# Lan_Tap_V1.net
KiCad netlist of a schematic drawn in EAGLE
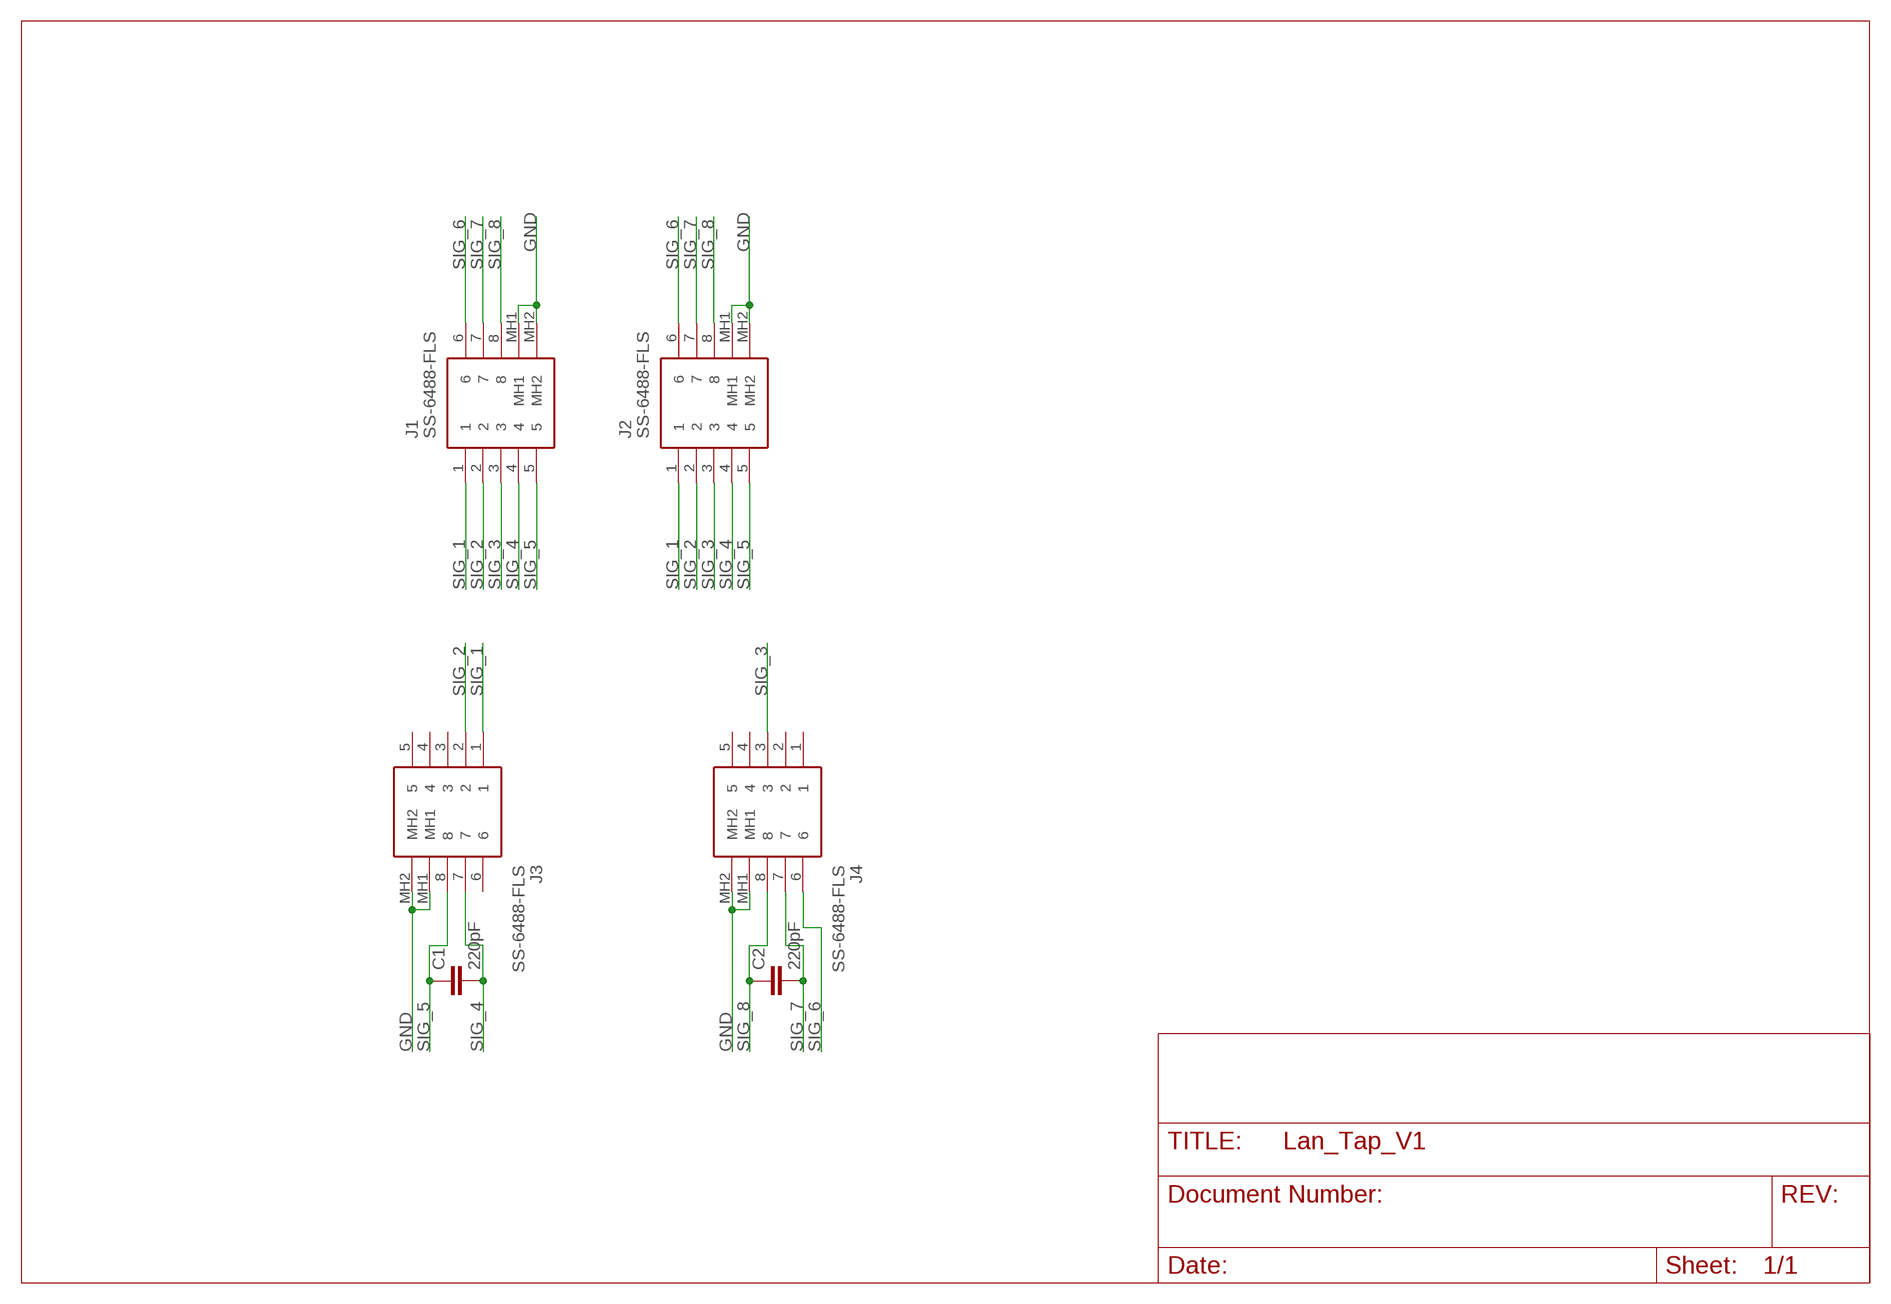
[diagram p0: schematic, sheet 1]

(export (version "E")
  (design (tool "Eeschema 10.0.6"))
  (components
    (comp (ref "C1")
      (value "220pF")
      (footprint "eagle-import:C2.5-2")
      (libsource (lib "eagle-import") (part "C2.5/2"))
    )
    (comp (ref "C2")
      (value "220pF")
      (footprint "eagle-import:C2.5-2")
      (libsource (lib "eagle-import") (part "C2.5/2"))
    )
    (comp (ref "J1")
      (value "SS-6488-FLS")
      (footprint "eagle-import:SS6488FLS")
      (fields (field (name "MOUSER_PART_NUMBER") "530-SS-6488-FLS"))
      (libsource (lib "eagle-import") (part "SS-6488-FLS"))
    )
    (comp (ref "J2")
      (value "SS-6488-FLS")
      (footprint "eagle-import:SS6488FLS")
      (fields (field (name "MOUSER_PART_NUMBER") "530-SS-6488-FLS"))
      (libsource (lib "eagle-import") (part "SS-6488-FLS"))
    )
    (comp (ref "J3")
      (value "SS-6488-FLS")
      (footprint "eagle-import:SS6488FLS")
      (fields (field (name "MOUSER_PART_NUMBER") "530-SS-6488-FLS"))
      (libsource (lib "eagle-import") (part "SS-6488-FLS"))
    )
    (comp (ref "J4")
      (value "SS-6488-FLS")
      (footprint "eagle-import:SS6488FLS")
      (fields (field (name "MOUSER_PART_NUMBER") "530-SS-6488-FLS"))
      (libsource (lib "eagle-import") (part "SS-6488-FLS"))
    )
  )
  (nets
    (net (code "1") (name "/GND") (class "Default")
      (node (ref "J1") (pin "MH1") (pinfunction "MH1_MH1") (pintype "bidirectional"))
      (node (ref "J1") (pin "MH2") (pinfunction "MH2_MH2") (pintype "bidirectional"))
      (node (ref "J2") (pin "MH1") (pinfunction "MH1_MH1") (pintype "bidirectional"))
      (node (ref "J2") (pin "MH2") (pinfunction "MH2_MH2") (pintype "bidirectional"))
      (node (ref "J3") (pin "MH1") (pinfunction "MH1_MH1") (pintype "bidirectional"))
      (node (ref "J3") (pin "MH2") (pinfunction "MH2_MH2") (pintype "bidirectional"))
      (node (ref "J4") (pin "MH1") (pinfunction "MH1_MH1") (pintype "bidirectional"))
      (node (ref "J4") (pin "MH2") (pinfunction "MH2_MH2") (pintype "bidirectional"))
    )
    (net (code "2") (name "/SIG_1") (class "Default")
      (node (ref "J1") (pin "1") (pinfunction "1_1") (pintype "bidirectional"))
      (node (ref "J2") (pin "1") (pinfunction "1_1") (pintype "bidirectional"))
      (node (ref "J3") (pin "1") (pinfunction "1_1") (pintype "bidirectional"))
    )
    (net (code "3") (name "/SIG_2") (class "Default")
      (node (ref "J1") (pin "2") (pinfunction "2_2") (pintype "bidirectional"))
      (node (ref "J2") (pin "2") (pinfunction "2_2") (pintype "bidirectional"))
      (node (ref "J3") (pin "2") (pinfunction "2_2") (pintype "bidirectional"))
    )
    (net (code "4") (name "/SIG_3") (class "Default")
      (node (ref "J1") (pin "3") (pinfunction "3_3") (pintype "bidirectional"))
      (node (ref "J2") (pin "3") (pinfunction "3_3") (pintype "bidirectional"))
      (node (ref "J4") (pin "3") (pinfunction "3_3") (pintype "bidirectional"))
    )
    (net (code "5") (name "/SIG_4") (class "Default")
      (node (ref "C1") (pin "2") (pinfunction "2_2") (pintype "passive"))
      (node (ref "J1") (pin "4") (pinfunction "4_4") (pintype "bidirectional"))
      (node (ref "J2") (pin "4") (pinfunction "4_4") (pintype "bidirectional"))
      (node (ref "J3") (pin "7") (pinfunction "7_7") (pintype "bidirectional"))
    )
    (net (code "6") (name "/SIG_5") (class "Default")
      (node (ref "C1") (pin "1") (pinfunction "1_1") (pintype "passive"))
      (node (ref "J1") (pin "5") (pinfunction "5_5") (pintype "bidirectional"))
      (node (ref "J2") (pin "5") (pinfunction "5_5") (pintype "bidirectional"))
      (node (ref "J3") (pin "8") (pinfunction "8_8") (pintype "bidirectional"))
    )
    (net (code "7") (name "/SIG_6") (class "Default")
      (node (ref "J1") (pin "6") (pinfunction "6_6") (pintype "bidirectional"))
      (node (ref "J2") (pin "6") (pinfunction "6_6") (pintype "bidirectional"))
      (node (ref "J4") (pin "6") (pinfunction "6_6") (pintype "bidirectional"))
    )
    (net (code "8") (name "/SIG_7") (class "Default")
      (node (ref "C2") (pin "2") (pinfunction "2_2") (pintype "passive"))
      (node (ref "J1") (pin "7") (pinfunction "7_7") (pintype "bidirectional"))
      (node (ref "J2") (pin "7") (pinfunction "7_7") (pintype "bidirectional"))
      (node (ref "J4") (pin "7") (pinfunction "7_7") (pintype "bidirectional"))
    )
    (net (code "9") (name "/SIG_8") (class "Default")
      (node (ref "C2") (pin "1") (pinfunction "1_1") (pintype "passive"))
      (node (ref "J1") (pin "8") (pinfunction "8_8") (pintype "bidirectional"))
      (node (ref "J2") (pin "8") (pinfunction "8_8") (pintype "bidirectional"))
      (node (ref "J4") (pin "8") (pinfunction "8_8") (pintype "bidirectional"))
    )
    (net (code "10") (name "unconnected-(J3-Pad3)") (class "Default")
      (node (ref "J3") (pin "3") (pinfunction "3_3") (pintype "bidirectional"))
    )
    (net (code "11") (name "unconnected-(J3-Pad4)") (class "Default")
      (node (ref "J3") (pin "4") (pinfunction "4_4") (pintype "bidirectional"))
    )
    (net (code "12") (name "unconnected-(J3-Pad5)") (class "Default")
      (node (ref "J3") (pin "5") (pinfunction "5_5") (pintype "bidirectional"))
    )
    (net (code "13") (name "unconnected-(J3-Pad6)") (class "Default")
      (node (ref "J3") (pin "6") (pinfunction "6_6") (pintype "bidirectional"))
    )
    (net (code "14") (name "unconnected-(J4-Pad1)") (class "Default")
      (node (ref "J4") (pin "1") (pinfunction "1_1") (pintype "bidirectional"))
    )
    (net (code "15") (name "unconnected-(J4-Pad2)") (class "Default")
      (node (ref "J4") (pin "2") (pinfunction "2_2") (pintype "bidirectional"))
    )
    (net (code "16") (name "unconnected-(J4-Pad4)") (class "Default")
      (node (ref "J4") (pin "4") (pinfunction "4_4") (pintype "bidirectional"))
    )
    (net (code "17") (name "unconnected-(J4-Pad5)") (class "Default")
      (node (ref "J4") (pin "5") (pinfunction "5_5") (pintype "bidirectional"))
    )
  )
)
